# atum.net
KiCad netlist of a schematic drawn in EAGLE
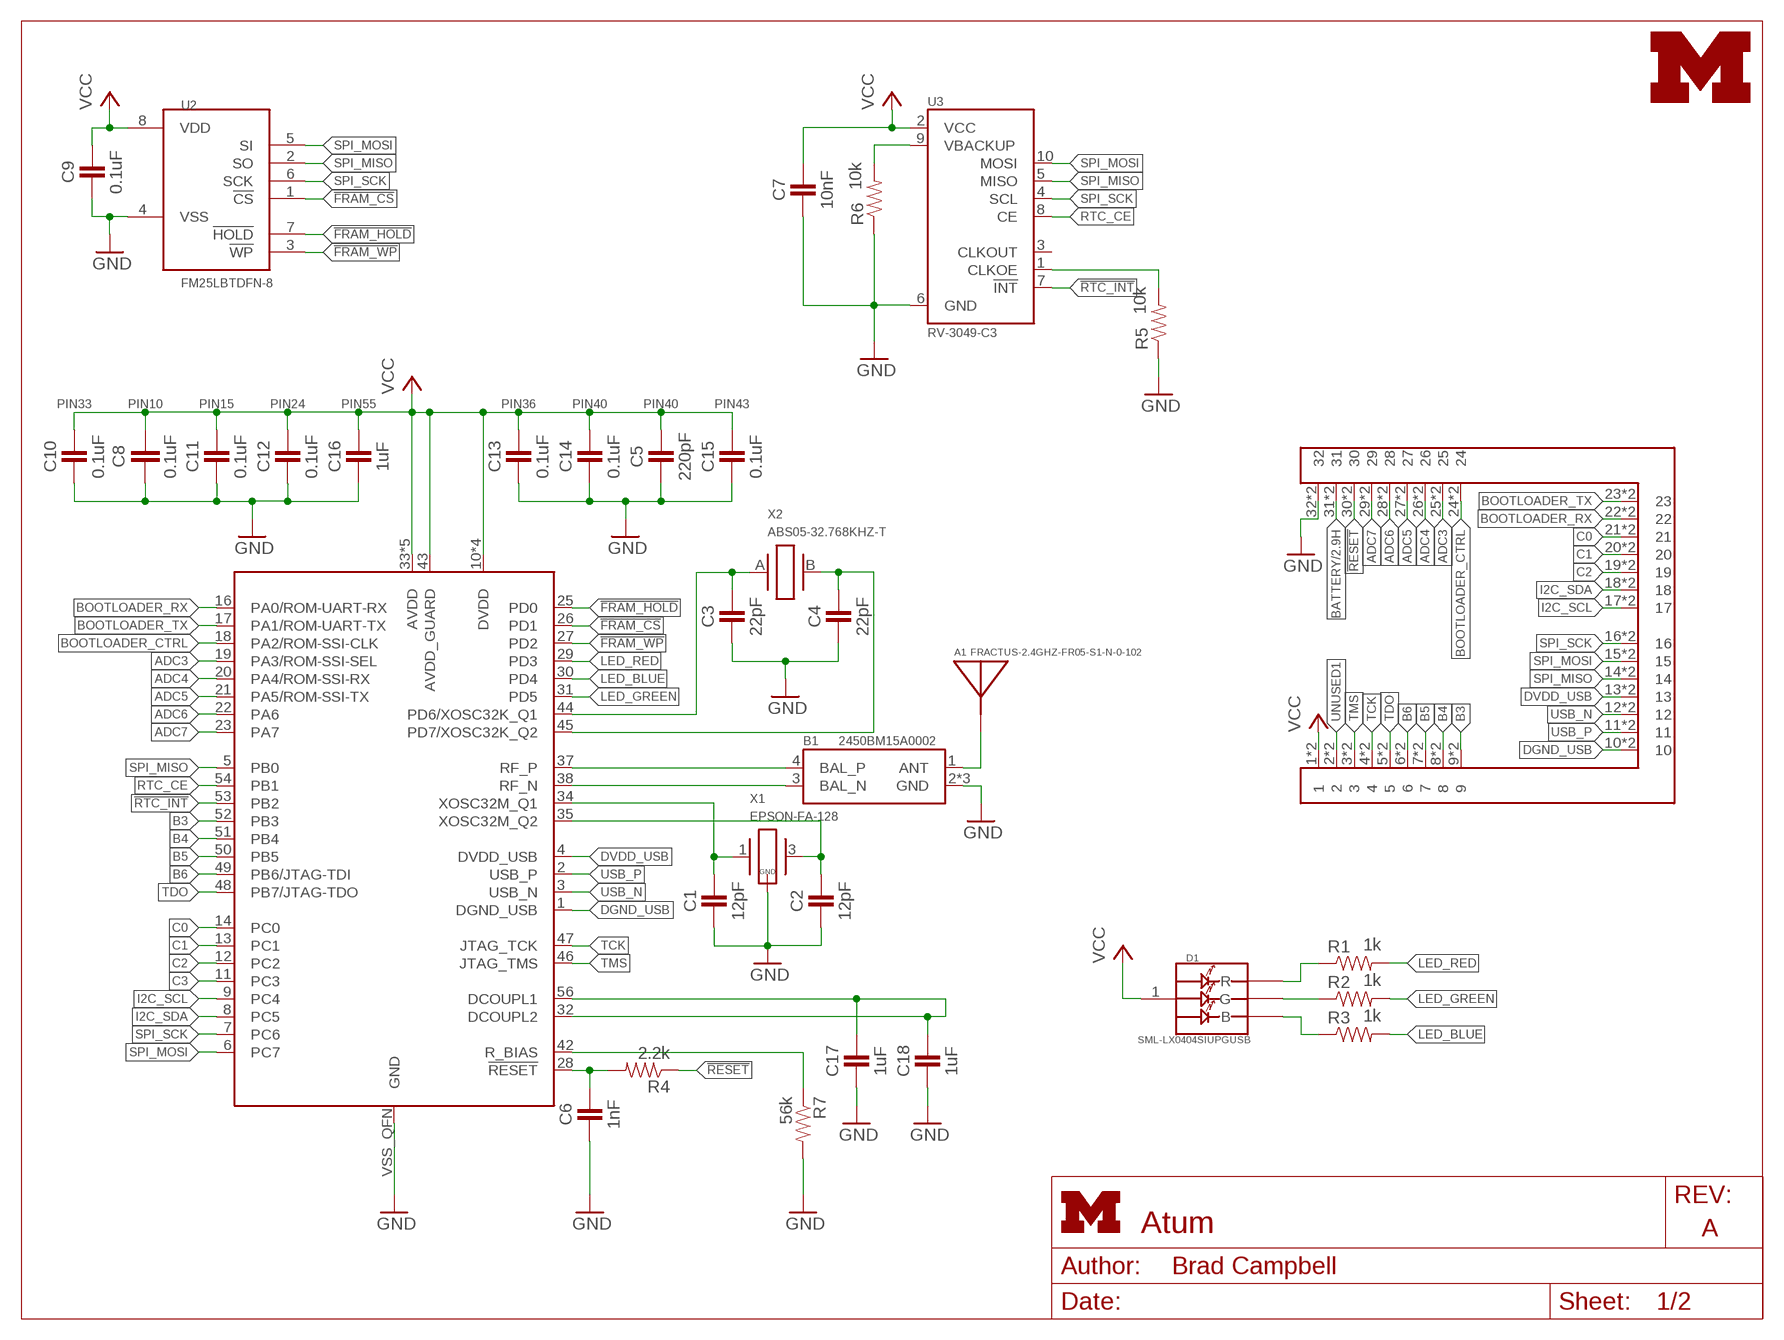
[diagram p0: schematic, sheet 1]
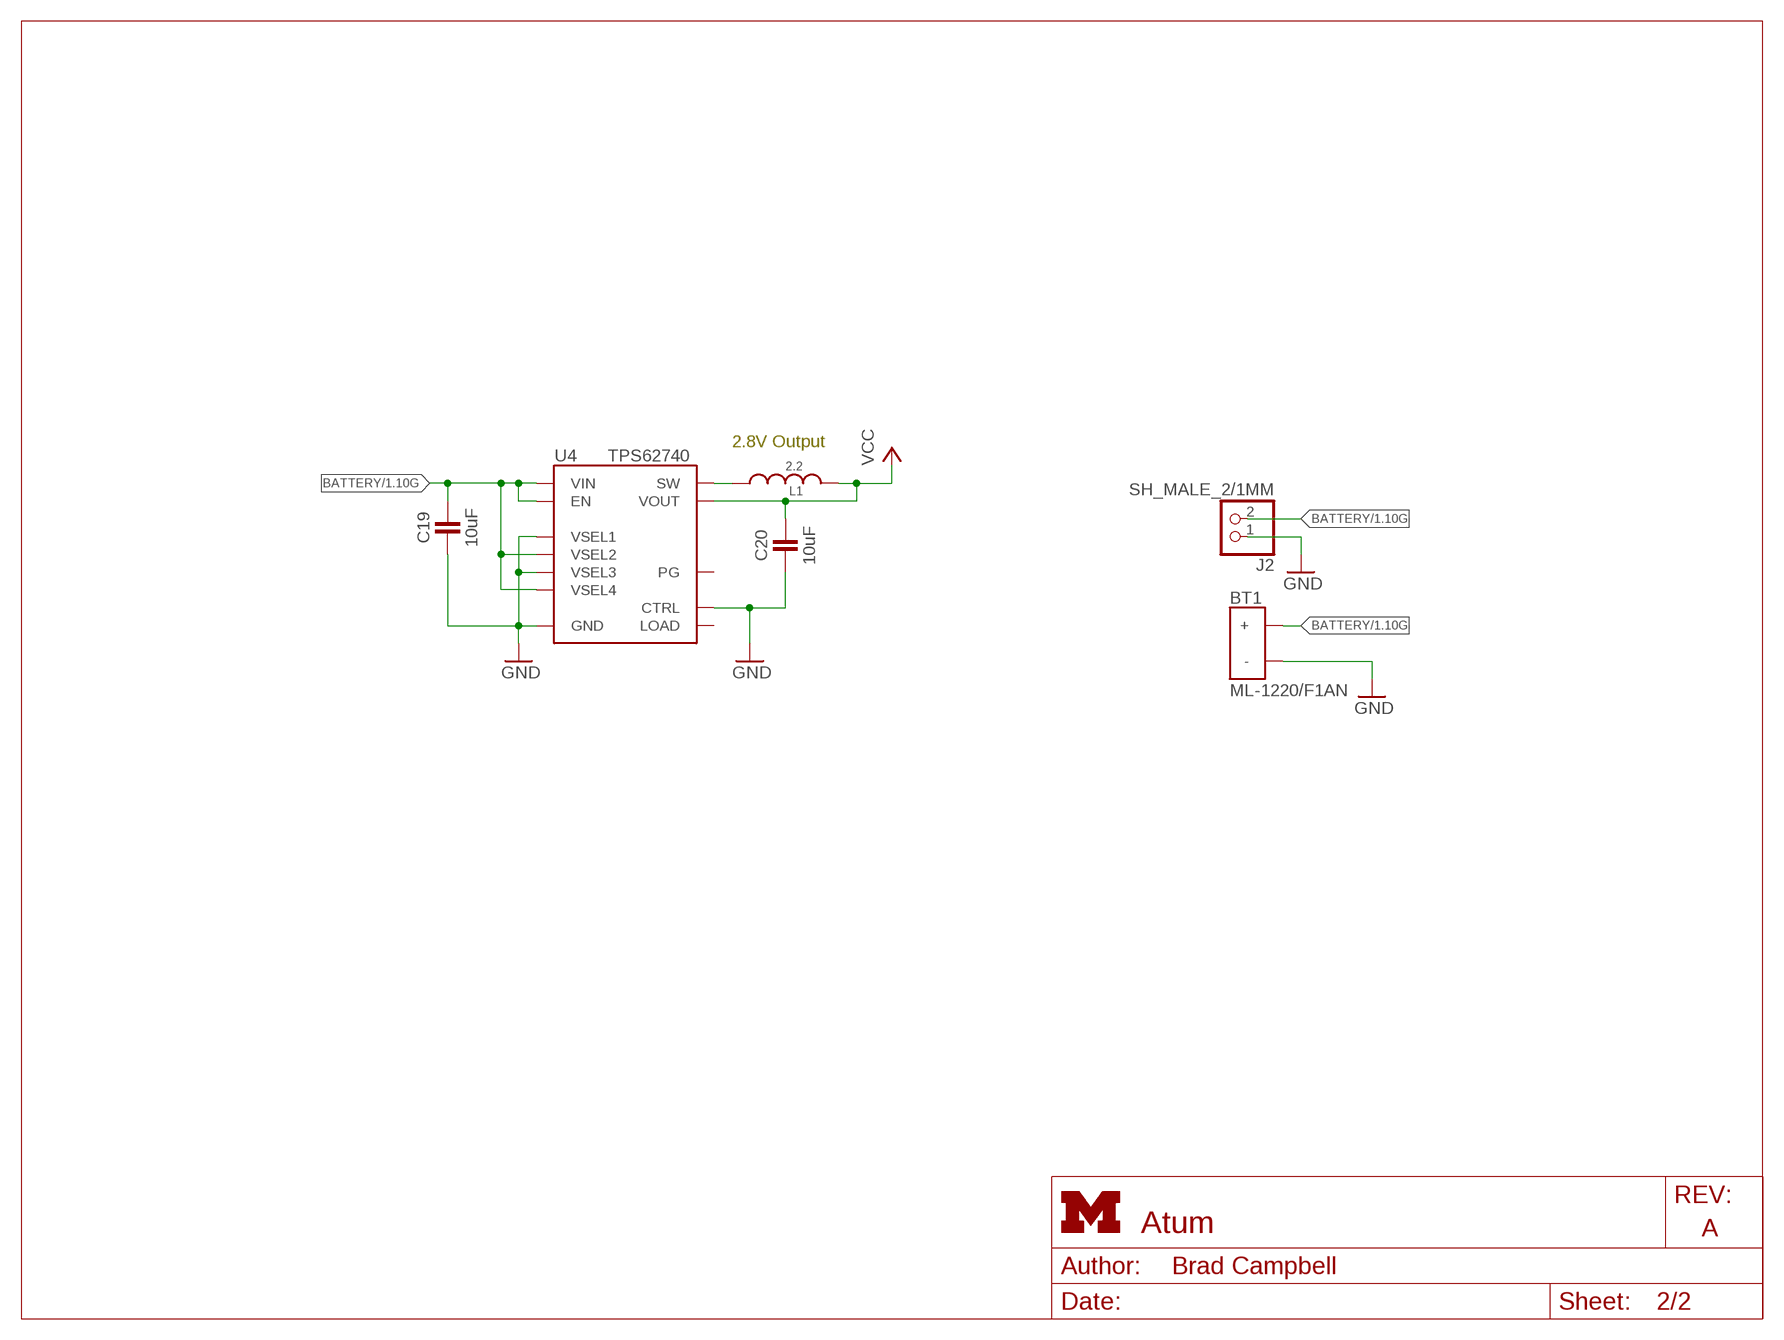
[diagram p1: schematic, sheet 2]

(export (version "E")
  (design (tool "Eeschema 10.0.6"))
  (components
    (comp (ref "A1")
      (value "FRACTUS-2.4GHZ-FR05-S1-N-0-102")
      (footprint "eagle-import:FRACTUS-ANTENNA-FR05-S1-N-0-102")
      (libsource (lib "eagle-import") (part "FRACTUS-2.4GHZ-FR05-S1-N-0-102"))
    )
    (comp (ref "B1")
      (value "2450BM15A0002")
      (footprint "eagle-import:2450BM")
      (libsource (lib "eagle-import") (part "2450BM15A0002"))
    )
    (comp (ref "C1")
      (value "12pF")
      (footprint "eagle-import:0402_CAP")
      (libsource (lib "eagle-import") (part "CAPACITOR"))
    )
    (comp (ref "C2")
      (value "12pF")
      (footprint "eagle-import:0402_CAP")
      (libsource (lib "eagle-import") (part "CAPACITOR"))
    )
    (comp (ref "C3")
      (value "22pF")
      (footprint "eagle-import:0402_CAP")
      (libsource (lib "eagle-import") (part "CAPACITOR"))
    )
    (comp (ref "C4")
      (value "22pF")
      (footprint "eagle-import:0402_CAP")
      (libsource (lib "eagle-import") (part "CAPACITOR"))
    )
    (comp (ref "C5")
      (value "220pF")
      (footprint "eagle-import:0402_CAP")
      (libsource (lib "eagle-import") (part "CAPACITOR"))
    )
    (comp (ref "C6")
      (value "1nF")
      (footprint "eagle-import:0402_CAP")
      (libsource (lib "eagle-import") (part "CAPACITOR"))
    )
    (comp (ref "C7")
      (value "10nF")
      (footprint "eagle-import:0402_CAP")
      (libsource (lib "eagle-import") (part "CAPACITOR"))
    )
    (comp (ref "C8")
      (value "0.1uF")
      (footprint "eagle-import:C0201")
      (libsource (lib "eagle-import") (part "C-EUC0201"))
    )
    (comp (ref "C9")
      (value "0.1uF")
      (footprint "eagle-import:0402_CAP")
      (libsource (lib "eagle-import") (part "CAPACITOR"))
    )
    (comp (ref "C10")
      (value "0.1uF")
      (footprint "eagle-import:0402_CAP")
      (libsource (lib "eagle-import") (part "CAPACITOR"))
    )
    (comp (ref "C11")
      (value "0.1uF")
      (footprint "eagle-import:0402_CAP")
      (libsource (lib "eagle-import") (part "CAPACITOR"))
    )
    (comp (ref "C12")
      (value "0.1uF")
      (footprint "eagle-import:0402_CAP")
      (libsource (lib "eagle-import") (part "CAPACITOR"))
    )
    (comp (ref "C13")
      (value "0.1uF")
      (footprint "eagle-import:0402_CAP")
      (libsource (lib "eagle-import") (part "CAPACITOR"))
    )
    (comp (ref "C14")
      (value "0.1uF")
      (footprint "eagle-import:0402_CAP")
      (libsource (lib "eagle-import") (part "CAPACITOR"))
    )
    (comp (ref "C15")
      (value "0.1uF")
      (footprint "eagle-import:0402_CAP")
      (libsource (lib "eagle-import") (part "CAPACITOR"))
    )
    (comp (ref "C16")
      (value "1uF")
      (footprint "eagle-import:0402_CAP")
      (libsource (lib "eagle-import") (part "CAPACITOR"))
    )
    (comp (ref "C17")
      (value "1uF")
      (footprint "eagle-import:0402_CAP")
      (libsource (lib "eagle-import") (part "CAPACITOR"))
    )
    (comp (ref "C18")
      (value "1uF")
      (footprint "eagle-import:0402_CAP")
      (libsource (lib "eagle-import") (part "CAPACITOR"))
    )
    (comp (ref "D1")
      (value "SML-LX0404SIUPGUSB")
      (footprint "eagle-import:1MM_SQ_4PAD")
      (libsource (lib "eagle-import") (part "SML-LX0404SIUPGUSB"))
    )
    (comp (ref "J3")
      (value "ATUM-HEADER")
      (footprint "eagle-import:ATUM-HEADER")
      (libsource (lib "eagle-import") (part "ATUM-HEADER"))
    )
    (comp (ref "LOGO1")
      (value "UMICH_SOLID_TINY")
      (footprint "eagle-import:UMICH_SOLID_50MIL")
      (libsource (lib "eagle-import") (part "UMICH_SOLID_TINY"))
    )
    (comp (ref "R1")
      (value "1k")
      (footprint "eagle-import:0402_RES")
      (libsource (lib "eagle-import") (part "RESISTOR"))
    )
    (comp (ref "R2")
      (value "1k")
      (footprint "eagle-import:0402_RES")
      (libsource (lib "eagle-import") (part "RESISTOR"))
    )
    (comp (ref "R3")
      (value "1k")
      (footprint "eagle-import:0402_RES")
      (libsource (lib "eagle-import") (part "RESISTOR"))
    )
    (comp (ref "R4")
      (value "2.2k")
      (footprint "eagle-import:0402_RES")
      (libsource (lib "eagle-import") (part "RESISTOR"))
    )
    (comp (ref "R5")
      (value "10k")
      (footprint "eagle-import:0402_RES")
      (libsource (lib "eagle-import") (part "RESISTOR"))
    )
    (comp (ref "R6")
      (value "10k")
      (footprint "eagle-import:0402_RES")
      (libsource (lib "eagle-import") (part "RESISTOR"))
    )
    (comp (ref "R7")
      (value "56k")
      (footprint "eagle-import:0402_RES")
      (libsource (lib "eagle-import") (part "RESISTOR"))
    )
    (comp (ref "U1")
      (value "CC2538")
      (footprint "eagle-import:S-PVQFN-N56")
      (libsource (lib "eagle-import") (part "CC2538"))
    )
    (comp (ref "U2")
      (value "FM25LBTDFN-8")
      (footprint "eagle-import:TDFN-8")
      (libsource (lib "eagle-import") (part "FM25LBTDFN-8"))
    )
    (comp (ref "U3")
      (value "RV-3049-C3")
      (footprint "eagle-import:MICRO-CRYSTAL-C3")
      (libsource (lib "eagle-import") (part "RV-3049-C3"))
    )
    (comp (ref "X1")
      (value "EPSON-FA-128")
      (footprint "eagle-import:FA-128")
      (libsource (lib "eagle-import") (part "EPSON-FA-128"))
    )
    (comp (ref "X2")
      (value "ABS05-32.768KHZ-T")
      (footprint "eagle-import:ABS05")
      (libsource (lib "eagle-import") (part "ABS05-32.768KHZ-T"))
    )
    (comp (ref "BT1")
      (value "ML-1220/F1AN")
      (footprint "eagle-import:ML-1220_F1BN")
      (libsource (lib "eagle-import") (part "ML-1220/F1AN"))
    )
    (comp (ref "C19")
      (value "10uF")
      (footprint "eagle-import:0603_CAP")
      (libsource (lib "eagle-import") (part "CAPACITOR0603_CAP"))
    )
    (comp (ref "C20")
      (value "10uF")
      (footprint "eagle-import:0603_CAP")
      (libsource (lib "eagle-import") (part "CAPACITOR0603_CAP"))
    )
    (comp (ref "J2")
      (value "SH_MALE_2/1MM")
      (footprint "eagle-import:SH-1X2_1MM")
      (libsource (lib "eagle-import") (part "SH_MALE_2/1MM"))
    )
    (comp (ref "L1")
      (value "2.2")
      (footprint "eagle-import:MIPSZ201D")
      (libsource (lib "eagle-import") (part "MIPSZ2012D"))
    )
    (comp (ref "U4")
      (value "TPS62740")
      (footprint "eagle-import:R-PWSON-12")
      (libsource (lib "eagle-import") (part "TPS62740"))
    )
  )
  (nets
    (net (code "1") (name "ADC3") (class "Default")
      (node (ref "J3") (pin "25") (pinfunction "25_25") (pintype "bidirectional"))
      (node (ref "J3") (pin "25B") (pinfunction "25_25B") (pintype "bidirectional"))
      (node (ref "U1") (pin "19") (pinfunction "PA3/ROM-SSI-SEL_19") (pintype "bidirectional"))
    )
    (net (code "2") (name "ADC4") (class "Default")
      (node (ref "J3") (pin "26") (pinfunction "26_26") (pintype "bidirectional"))
      (node (ref "J3") (pin "26B") (pinfunction "26_26B") (pintype "bidirectional"))
      (node (ref "U1") (pin "20") (pinfunction "PA4/ROM-SSI-RX_20") (pintype "bidirectional"))
    )
    (net (code "3") (name "ADC5") (class "Default")
      (node (ref "J3") (pin "27") (pinfunction "27_27") (pintype "bidirectional"))
      (node (ref "J3") (pin "27B") (pinfunction "27_27B") (pintype "bidirectional"))
      (node (ref "U1") (pin "21") (pinfunction "PA5/ROM-SSI-TX_21") (pintype "bidirectional"))
    )
    (net (code "4") (name "ADC6") (class "Default")
      (node (ref "J3") (pin "28") (pinfunction "28_28") (pintype "bidirectional"))
      (node (ref "J3") (pin "28B") (pinfunction "28_28B") (pintype "bidirectional"))
      (node (ref "U1") (pin "22") (pinfunction "PA6_22") (pintype "bidirectional"))
    )
    (net (code "5") (name "ADC7") (class "Default")
      (node (ref "J3") (pin "29") (pinfunction "29_29") (pintype "bidirectional"))
      (node (ref "J3") (pin "29B") (pinfunction "29_29B") (pintype "bidirectional"))
      (node (ref "U1") (pin "23") (pinfunction "PA7_23") (pintype "bidirectional"))
    )
    (net (code "6") (name "B3") (class "Default")
      (node (ref "J3") (pin "9") (pinfunction "9_9") (pintype "bidirectional"))
      (node (ref "J3") (pin "9B") (pinfunction "9_9B") (pintype "bidirectional"))
      (node (ref "U1") (pin "52") (pinfunction "PB3_52") (pintype "bidirectional"))
    )
    (net (code "7") (name "B4") (class "Default")
      (node (ref "J3") (pin "8") (pinfunction "8_8") (pintype "bidirectional"))
      (node (ref "J3") (pin "8B") (pinfunction "8_8B") (pintype "bidirectional"))
      (node (ref "U1") (pin "51") (pinfunction "PB4_51") (pintype "bidirectional"))
    )
    (net (code "8") (name "B5") (class "Default")
      (node (ref "J3") (pin "7") (pinfunction "7_7") (pintype "bidirectional"))
      (node (ref "J3") (pin "7B") (pinfunction "7_7B") (pintype "bidirectional"))
      (node (ref "U1") (pin "50") (pinfunction "PB5_50") (pintype "bidirectional"))
    )
    (net (code "9") (name "B6") (class "Default")
      (node (ref "J3") (pin "6") (pinfunction "6_6") (pintype "bidirectional"))
      (node (ref "J3") (pin "6B") (pinfunction "6_6B") (pintype "bidirectional"))
      (node (ref "U1") (pin "49") (pinfunction "PB6/JTAG-TDI_49") (pintype "bidirectional"))
    )
    (net (code "10") (name "BATTERY") (class "Default")
      (node (ref "BT1") (pin "POS") (pinfunction "+_POS") (pintype "bidirectional"))
      (node (ref "C19") (pin "1") (pinfunction "1_1") (pintype "bidirectional"))
      (node (ref "J2") (pin "2") (pinfunction "2_2") (pintype "passive"))
      (node (ref "J3") (pin "31") (pinfunction "31_31") (pintype "bidirectional"))
      (node (ref "J3") (pin "31B") (pinfunction "31_31B") (pintype "bidirectional"))
      (node (ref "U4") (pin "1") (pinfunction "VIN_1") (pintype "bidirectional"))
      (node (ref "U4") (pin "10") (pinfunction "VSEL2_10") (pintype "bidirectional"))
      (node (ref "U4") (pin "12") (pinfunction "EN_12") (pintype "bidirectional"))
      (node (ref "U4") (pin "8") (pinfunction "VSEL4_8") (pintype "bidirectional"))
    )
    (net (code "11") (name "BOOTLOADER_CTRL") (class "Default")
      (node (ref "J3") (pin "24") (pinfunction "24_24") (pintype "bidirectional"))
      (node (ref "J3") (pin "24B") (pinfunction "24_24B") (pintype "bidirectional"))
      (node (ref "U1") (pin "18") (pinfunction "PA2/ROM-SSI-CLK_18") (pintype "bidirectional"))
    )
    (net (code "12") (name "BOOTLOADER_RX") (class "Default")
      (node (ref "J3") (pin "22") (pinfunction "22_22") (pintype "bidirectional"))
      (node (ref "J3") (pin "22B") (pinfunction "22_22B") (pintype "bidirectional"))
      (node (ref "U1") (pin "16") (pinfunction "PA0/ROM-UART-RX_16") (pintype "bidirectional"))
    )
    (net (code "13") (name "BOOTLOADER_TX") (class "Default")
      (node (ref "J3") (pin "23") (pinfunction "23_23") (pintype "bidirectional"))
      (node (ref "J3") (pin "23B") (pinfunction "23_23B") (pintype "bidirectional"))
      (node (ref "U1") (pin "17") (pinfunction "PA1/ROM-UART-TX_17") (pintype "bidirectional"))
    )
    (net (code "14") (name "C0") (class "Default")
      (node (ref "J3") (pin "21") (pinfunction "21_21") (pintype "bidirectional"))
      (node (ref "J3") (pin "21B") (pinfunction "21_21B") (pintype "bidirectional"))
      (node (ref "U1") (pin "14") (pinfunction "PC0_14") (pintype "bidirectional"))
    )
    (net (code "15") (name "C1") (class "Default")
      (node (ref "J3") (pin "20") (pinfunction "20_20") (pintype "bidirectional"))
      (node (ref "J3") (pin "20B") (pinfunction "20_20B") (pintype "bidirectional"))
      (node (ref "U1") (pin "13") (pinfunction "PC1_13") (pintype "bidirectional"))
    )
    (net (code "16") (name "C2") (class "Default")
      (node (ref "J3") (pin "19") (pinfunction "19_19") (pintype "bidirectional"))
      (node (ref "J3") (pin "19B") (pinfunction "19_19B") (pintype "bidirectional"))
      (node (ref "U1") (pin "12") (pinfunction "PC2_12") (pintype "bidirectional"))
    )
    (net (code "17") (name "C3") (class "Default")
      (node (ref "U1") (pin "11") (pinfunction "PC3_11") (pintype "bidirectional"))
    )
    (net (code "18") (name "DGND_USB") (class "Default")
      (node (ref "J3") (pin "10") (pinfunction "10_10") (pintype "bidirectional"))
      (node (ref "J3") (pin "10B") (pinfunction "10_10B") (pintype "bidirectional"))
      (node (ref "U1") (pin "1") (pinfunction "DGND_USB_1") (pintype "bidirectional"))
    )
    (net (code "19") (name "DVDD_USB") (class "Default")
      (node (ref "J3") (pin "13") (pinfunction "13_13") (pintype "bidirectional"))
      (node (ref "J3") (pin "13B") (pinfunction "13_13B") (pintype "bidirectional"))
      (node (ref "U1") (pin "4") (pinfunction "DVDD_USB_4") (pintype "bidirectional"))
    )
    (net (code "20") (name "GND") (class "Default")
      (node (ref "B1") (pin "2") (pinfunction "GND_2") (pintype "bidirectional"))
      (node (ref "B1") (pin "5") (pinfunction "GND_5") (pintype "bidirectional"))
      (node (ref "B1") (pin "6") (pinfunction "GND_6") (pintype "bidirectional"))
      (node (ref "BT1") (pin "NEG") (pinfunction "-_NEG") (pintype "bidirectional"))
      (node (ref "C1") (pin "2") (pinfunction "2_2") (pintype "bidirectional"))
      (node (ref "C10") (pin "2") (pinfunction "2_2") (pintype "bidirectional"))
      (node (ref "C11") (pin "2") (pinfunction "2_2") (pintype "bidirectional"))
      (node (ref "C12") (pin "2") (pinfunction "2_2") (pintype "bidirectional"))
      (node (ref "C13") (pin "2") (pinfunction "2_2") (pintype "bidirectional"))
      (node (ref "C14") (pin "2") (pinfunction "2_2") (pintype "bidirectional"))
      (node (ref "C15") (pin "2") (pinfunction "2_2") (pintype "bidirectional"))
      (node (ref "C16") (pin "2") (pinfunction "2_2") (pintype "bidirectional"))
      (node (ref "C17") (pin "2") (pinfunction "2_2") (pintype "bidirectional"))
      (node (ref "C18") (pin "2") (pinfunction "2_2") (pintype "bidirectional"))
      (node (ref "C19") (pin "2") (pinfunction "2_2") (pintype "bidirectional"))
      (node (ref "C2") (pin "2") (pinfunction "2_2") (pintype "bidirectional"))
      (node (ref "C20") (pin "2") (pinfunction "2_2") (pintype "bidirectional"))
      (node (ref "C3") (pin "2") (pinfunction "2_2") (pintype "bidirectional"))
      (node (ref "C4") (pin "2") (pinfunction "2_2") (pintype "bidirectional"))
      (node (ref "C5") (pin "2") (pinfunction "2_2") (pintype "bidirectional"))
      (node (ref "C6") (pin "2") (pinfunction "2_2") (pintype "bidirectional"))
      (node (ref "C7") (pin "2") (pinfunction "2_2") (pintype "bidirectional"))
      (node (ref "C8") (pin "2") (pinfunction "2_2") (pintype "passive"))
      (node (ref "C9") (pin "2") (pinfunction "2_2") (pintype "bidirectional"))
      (node (ref "J2") (pin "1") (pinfunction "1_1") (pintype "passive"))
      (node (ref "J3") (pin "32") (pinfunction "32_32") (pintype "bidirectional"))
      (node (ref "J3") (pin "32B") (pinfunction "32_32B") (pintype "bidirectional"))
      (node (ref "R5") (pin "1") (pinfunction "1_1") (pintype "passive"))
      (node (ref "R6") (pin "1") (pinfunction "1_1") (pintype "passive"))
      (node (ref "R7") (pin "2") (pinfunction "2_2") (pintype "passive"))
      (node (ref "U1") (pin "VSS_QFN") (pinfunction "GND_VSS_QFN") (pintype "bidirectional"))
      (node (ref "U2") (pin "4") (pinfunction "VSS_4") (pintype "bidirectional"))
      (node (ref "U3") (pin "6") (pinfunction "GND_6") (pintype "bidirectional"))
      (node (ref "U4") (pin "11") (pinfunction "VSEL1_11") (pintype "bidirectional"))
      (node (ref "U4") (pin "3") (pinfunction "GND_3") (pintype "bidirectional"))
      (node (ref "U4") (pin "4") (pinfunction "CTRL_4") (pintype "bidirectional"))
      (node (ref "U4") (pin "9") (pinfunction "VSEL3_9") (pintype "bidirectional"))
      (node (ref "U4") (pin "NC") (pinfunction "GND_NC") (pintype "bidirectional"))
      (node (ref "X1") (pin "2") (pinfunction "GND_2") (pintype "bidirectional"))
      (node (ref "X1") (pin "4") (pinfunction "GND_4") (pintype "bidirectional"))
    )
    (net (code "21") (name "I2C_SCL") (class "Default")
      (node (ref "J3") (pin "17") (pinfunction "17_17") (pintype "bidirectional"))
      (node (ref "J3") (pin "17B") (pinfunction "17_17B") (pintype "bidirectional"))
      (node (ref "U1") (pin "9") (pinfunction "PC4_9") (pintype "bidirectional"))
    )
    (net (code "22") (name "I2C_SDA") (class "Default")
      (node (ref "J3") (pin "18") (pinfunction "18_18") (pintype "bidirectional"))
      (node (ref "J3") (pin "18B") (pinfunction "18_18B") (pintype "bidirectional"))
      (node (ref "U1") (pin "8") (pinfunction "PC5_8") (pintype "bidirectional"))
    )
    (net (code "23") (name "LED_BLUE") (class "Default")
      (node (ref "R3") (pin "2") (pinfunction "2_2") (pintype "passive"))
      (node (ref "U1") (pin "30") (pinfunction "PD4_30") (pintype "bidirectional"))
    )
    (net (code "24") (name "LED_GREEN") (class "Default")
      (node (ref "R2") (pin "2") (pinfunction "2_2") (pintype "passive"))
      (node (ref "U1") (pin "31") (pinfunction "PD5_31") (pintype "bidirectional"))
    )
    (net (code "25") (name "LED_RED") (class "Default")
      (node (ref "R1") (pin "2") (pinfunction "2_2") (pintype "passive"))
      (node (ref "U1") (pin "29") (pinfunction "PD3_29") (pintype "bidirectional"))
    )
    (net (code "26") (name "Net-(A1-ANTENNA)") (class "Default")
      (node (ref "A1") (pin "1") (pinfunction "ANTENNA_1") (pintype "bidirectional"))
      (node (ref "B1") (pin "1") (pinfunction "ANT_1") (pintype "bidirectional"))
    )
    (net (code "27") (name "Net-(B1-BAL_N)") (class "Default")
      (node (ref "B1") (pin "3") (pinfunction "BAL_N_3") (pintype "bidirectional"))
      (node (ref "U1") (pin "38") (pinfunction "RF_N_38") (pintype "bidirectional"))
    )
    (net (code "28") (name "Net-(B1-BAL_P)") (class "Default")
      (node (ref "B1") (pin "4") (pinfunction "BAL_P_4") (pintype "bidirectional"))
      (node (ref "U1") (pin "37") (pinfunction "RF_P_37") (pintype "bidirectional"))
    )
    (net (code "29") (name "Net-(D1-B)") (class "Default")
      (node (ref "D1") (pin "3") (pinfunction "B_3") (pintype "output"))
      (node (ref "R3") (pin "1") (pinfunction "1_1") (pintype "passive"))
    )
    (net (code "30") (name "Net-(D1-G)") (class "Default")
      (node (ref "D1") (pin "4") (pinfunction "G_4") (pintype "output"))
      (node (ref "R2") (pin "1") (pinfunction "1_1") (pintype "passive"))
    )
    (net (code "31") (name "Net-(D1-R)") (class "Default")
      (node (ref "D1") (pin "2") (pinfunction "R_2") (pintype "output"))
      (node (ref "R1") (pin "1") (pinfunction "1_1") (pintype "passive"))
    )
    (net (code "32") (name "Net-(U1-DCOUPL1)") (class "Default")
      (node (ref "C17") (pin "1") (pinfunction "1_1") (pintype "bidirectional"))
      (node (ref "C18") (pin "1") (pinfunction "1_1") (pintype "bidirectional"))
      (node (ref "U1") (pin "32") (pinfunction "DCOUPL2_32") (pintype "bidirectional"))
      (node (ref "U1") (pin "56") (pinfunction "DCOUPL1_56") (pintype "bidirectional"))
    )
    (net (code "33") (name "Net-(U1-PD6{slash}XOSC32K_Q1)") (class "Default")
      (node (ref "C3") (pin "1") (pinfunction "1_1") (pintype "bidirectional"))
      (node (ref "U1") (pin "44") (pinfunction "PD6/XOSC32K_Q1_44") (pintype "bidirectional"))
      (node (ref "X2") (pin "A") (pinfunction "1_A") (pintype "bidirectional"))
    )
    (net (code "34") (name "Net-(U1-PD7{slash}XOSC32K_Q2)") (class "Default")
      (node (ref "C4") (pin "1") (pinfunction "1_1") (pintype "bidirectional"))
      (node (ref "U1") (pin "45") (pinfunction "PD7/XOSC32K_Q2_45") (pintype "bidirectional"))
      (node (ref "X2") (pin "B") (pinfunction "2_B") (pintype "bidirectional"))
    )
    (net (code "35") (name "Net-(U1-R_BIAS)") (class "Default")
      (node (ref "R7") (pin "1") (pinfunction "1_1") (pintype "passive"))
      (node (ref "U1") (pin "42") (pinfunction "R_BIAS_42") (pintype "bidirectional"))
    )
    (net (code "36") (name "Net-(U1-XOSC32M_Q1)") (class "Default")
      (node (ref "C1") (pin "1") (pinfunction "1_1") (pintype "bidirectional"))
      (node (ref "U1") (pin "34") (pinfunction "XOSC32M_Q1_34") (pintype "bidirectional"))
      (node (ref "X1") (pin "1") (pinfunction "1_1") (pintype "bidirectional"))
    )
    (net (code "37") (name "Net-(U1-XOSC32M_Q2)") (class "Default")
      (node (ref "C2") (pin "1") (pinfunction "1_1") (pintype "bidirectional"))
      (node (ref "U1") (pin "35") (pinfunction "XOSC32M_Q2_35") (pintype "bidirectional"))
      (node (ref "X1") (pin "3") (pinfunction "2_3") (pintype "bidirectional"))
    )
    (net (code "38") (name "Net-(U1-~{RESET})") (class "Default")
      (node (ref "C6") (pin "1") (pinfunction "1_1") (pintype "bidirectional"))
      (node (ref "R4") (pin "2") (pinfunction "2_2") (pintype "passive"))
      (node (ref "U1") (pin "28") (pinfunction "~{RESET}_28") (pintype "bidirectional"))
    )
    (net (code "39") (name "Net-(U3-CLKOE)") (class "Default")
      (node (ref "R5") (pin "2") (pinfunction "2_2") (pintype "passive"))
      (node (ref "U3") (pin "1") (pinfunction "CLKOE_1") (pintype "bidirectional"))
    )
    (net (code "40") (name "Net-(U3-VBACKUP)") (class "Default")
      (node (ref "R6") (pin "2") (pinfunction "2_2") (pintype "passive"))
      (node (ref "U3") (pin "9") (pinfunction "VBACKUP_9") (pintype "bidirectional"))
    )
    (net (code "41") (name "Net-(U4-SW)") (class "Default")
      (node (ref "L1") (pin "1") (pinfunction "1_1") (pintype "bidirectional"))
      (node (ref "U4") (pin "2") (pinfunction "SW_2") (pintype "bidirectional"))
    )
    (net (code "42") (name "RTC_CE") (class "Default")
      (node (ref "U1") (pin "54") (pinfunction "PB1_54") (pintype "bidirectional"))
      (node (ref "U3") (pin "8") (pinfunction "CE_8") (pintype "bidirectional"))
    )
    (net (code "43") (name "SPI_MISO") (class "Default")
      (node (ref "J3") (pin "14") (pinfunction "14_14") (pintype "bidirectional"))
      (node (ref "J3") (pin "14B") (pinfunction "14_14B") (pintype "bidirectional"))
      (node (ref "U1") (pin "5") (pinfunction "PB0_5") (pintype "bidirectional"))
      (node (ref "U2") (pin "2") (pinfunction "SO_2") (pintype "bidirectional"))
      (node (ref "U3") (pin "5") (pinfunction "MISO_5") (pintype "bidirectional"))
    )
    (net (code "44") (name "SPI_MOSI") (class "Default")
      (node (ref "J3") (pin "15") (pinfunction "15_15") (pintype "bidirectional"))
      (node (ref "J3") (pin "15B") (pinfunction "15_15B") (pintype "bidirectional"))
      (node (ref "U1") (pin "6") (pinfunction "PC7_6") (pintype "bidirectional"))
      (node (ref "U2") (pin "5") (pinfunction "SI_5") (pintype "bidirectional"))
      (node (ref "U3") (pin "10") (pinfunction "MOSI_10") (pintype "bidirectional"))
    )
    (net (code "45") (name "SPI_SCK") (class "Default")
      (node (ref "J3") (pin "16") (pinfunction "16_16") (pintype "bidirectional"))
      (node (ref "J3") (pin "16B") (pinfunction "16_16B") (pintype "bidirectional"))
      (node (ref "U1") (pin "7") (pinfunction "PC6_7") (pintype "bidirectional"))
      (node (ref "U2") (pin "6") (pinfunction "SCK_6") (pintype "bidirectional"))
      (node (ref "U3") (pin "4") (pinfunction "SCL_4") (pintype "bidirectional"))
    )
    (net (code "46") (name "TCK") (class "Default")
      (node (ref "J3") (pin "4") (pinfunction "4_4") (pintype "bidirectional"))
      (node (ref "J3") (pin "4B") (pinfunction "4_4B") (pintype "bidirectional"))
      (node (ref "U1") (pin "47") (pinfunction "JTAG_TCK_47") (pintype "bidirectional"))
    )
    (net (code "47") (name "TDO") (class "Default")
      (node (ref "J3") (pin "5") (pinfunction "5_5") (pintype "bidirectional"))
      (node (ref "J3") (pin "5B") (pinfunction "5_5B") (pintype "bidirectional"))
      (node (ref "U1") (pin "48") (pinfunction "PB7/JTAG-TDO_48") (pintype "bidirectional"))
    )
    (net (code "48") (name "TMS") (class "Default")
      (node (ref "J3") (pin "3") (pinfunction "3_3") (pintype "bidirectional"))
      (node (ref "J3") (pin "3B") (pinfunction "3_3B") (pintype "bidirectional"))
      (node (ref "U1") (pin "46") (pinfunction "JTAG_TMS_46") (pintype "bidirectional"))
    )
    (net (code "49") (name "UNUSED1") (class "Default")
      (node (ref "J3") (pin "2") (pinfunction "2_2") (pintype "bidirectional"))
      (node (ref "J3") (pin "2B") (pinfunction "2_2B") (pintype "bidirectional"))
    )
    (net (code "50") (name "USB_N") (class "Default")
      (node (ref "J3") (pin "12") (pinfunction "12_12") (pintype "bidirectional"))
      (node (ref "J3") (pin "12B") (pinfunction "12_12B") (pintype "bidirectional"))
      (node (ref "U1") (pin "3") (pinfunction "USB_N_3") (pintype "bidirectional"))
    )
    (net (code "51") (name "USB_P") (class "Default")
      (node (ref "J3") (pin "11") (pinfunction "11_11") (pintype "bidirectional"))
      (node (ref "J3") (pin "11B") (pinfunction "11_11B") (pintype "bidirectional"))
      (node (ref "U1") (pin "2") (pinfunction "USB_P_2") (pintype "bidirectional"))
    )
    (net (code "52") (name "VCC") (class "Default")
      (node (ref "C10") (pin "1") (pinfunction "1_1") (pintype "bidirectional"))
      (node (ref "C11") (pin "1") (pinfunction "1_1") (pintype "bidirectional"))
      (node (ref "C12") (pin "1") (pinfunction "1_1") (pintype "bidirectional"))
      (node (ref "C13") (pin "1") (pinfunction "1_1") (pintype "bidirectional"))
      (node (ref "C14") (pin "1") (pinfunction "1_1") (pintype "bidirectional"))
      (node (ref "C15") (pin "1") (pinfunction "1_1") (pintype "bidirectional"))
      (node (ref "C16") (pin "1") (pinfunction "1_1") (pintype "bidirectional"))
      (node (ref "C20") (pin "1") (pinfunction "1_1") (pintype "bidirectional"))
      (node (ref "C5") (pin "1") (pinfunction "1_1") (pintype "bidirectional"))
      (node (ref "C7") (pin "1") (pinfunction "1_1") (pintype "bidirectional"))
      (node (ref "C8") (pin "1") (pinfunction "1_1") (pintype "passive"))
      (node (ref "C9") (pin "1") (pinfunction "1_1") (pintype "bidirectional"))
      (node (ref "D1") (pin "1") (pinfunction "VDD_1") (pintype "bidirectional"))
      (node (ref "J3") (pin "1") (pinfunction "1_1") (pintype "bidirectional"))
      (node (ref "J3") (pin "1B") (pinfunction "1_1B") (pintype "bidirectional"))
      (node (ref "L1") (pin "2") (pinfunction "2_2") (pintype "bidirectional"))
      (node (ref "U1") (pin "10") (pinfunction "DVDD_10") (pintype "bidirectional"))
      (node (ref "U1") (pin "15") (pinfunction "DVDD_15") (pintype "bidirectional"))
      (node (ref "U1") (pin "24") (pinfunction "DVDD_24") (pintype "bidirectional"))
      (node (ref "U1") (pin "33") (pinfunction "AVDD_33") (pintype "bidirectional"))
      (node (ref "U1") (pin "36") (pinfunction "AVDD_36") (pintype "bidirectional"))
      (node (ref "U1") (pin "39") (pinfunction "AVDD_39") (pintype "bidirectional"))
      (node (ref "U1") (pin "40") (pinfunction "AVDD_40") (pintype "bidirectional"))
      (node (ref "U1") (pin "41") (pinfunction "AVDD_41") (pintype "bidirectional"))
      (node (ref "U1") (pin "43") (pinfunction "AVDD_GUARD_43") (pintype "bidirectional"))
      (node (ref "U1") (pin "55") (pinfunction "DVDD_55") (pintype "bidirectional"))
      (node (ref "U2") (pin "8") (pinfunction "VDD_8") (pintype "bidirectional"))
      (node (ref "U3") (pin "2") (pinfunction "VCC_2") (pintype "bidirectional"))
      (node (ref "U4") (pin "5") (pinfunction "VOUT_5") (pintype "bidirectional"))
    )
    (net (code "53") (name "unconnected-(U3-CLKOUT-Pad3)") (class "Default")
      (node (ref "U3") (pin "3") (pinfunction "CLKOUT_3") (pintype "bidirectional"))
    )
    (net (code "54") (name "unconnected-(U4-LOAD-Pad6)") (class "Default")
      (node (ref "U4") (pin "6") (pinfunction "LOAD_6") (pintype "bidirectional"))
    )
    (net (code "55") (name "unconnected-(U4-PG-Pad7)") (class "Default")
      (node (ref "U4") (pin "7") (pinfunction "PG_7") (pintype "bidirectional"))
    )
    (net (code "56") (name "~{FRAM_CS}") (class "Default")
      (node (ref "U1") (pin "26") (pinfunction "PD1_26") (pintype "bidirectional"))
      (node (ref "U2") (pin "1") (pinfunction "~{CS}_1") (pintype "bidirectional"))
    )
    (net (code "57") (name "~{FRAM_HOLD}") (class "Default")
      (node (ref "U1") (pin "25") (pinfunction "PD0_25") (pintype "bidirectional"))
      (node (ref "U2") (pin "7") (pinfunction "~{HOLD}_7") (pintype "bidirectional"))
    )
    (net (code "58") (name "~{FRAM_WP}") (class "Default")
      (node (ref "U1") (pin "27") (pinfunction "PD2_27") (pintype "bidirectional"))
      (node (ref "U2") (pin "3") (pinfunction "~{WP}_3") (pintype "bidirectional"))
    )
    (net (code "59") (name "~{RESET}") (class "Default")
      (node (ref "J3") (pin "30") (pinfunction "30_30") (pintype "bidirectional"))
      (node (ref "J3") (pin "30B") (pinfunction "30_30B") (pintype "bidirectional"))
      (node (ref "R4") (pin "1") (pinfunction "1_1") (pintype "passive"))
    )
    (net (code "60") (name "~{RTC_INT}") (class "Default")
      (node (ref "U1") (pin "53") (pinfunction "PB2_53") (pintype "bidirectional"))
      (node (ref "U3") (pin "7") (pinfunction "~{INT}_7") (pintype "bidirectional"))
    )
  )
)
